# MATRIZ_8x8.net
KiCad netlist of a schematic drawn in EAGLE
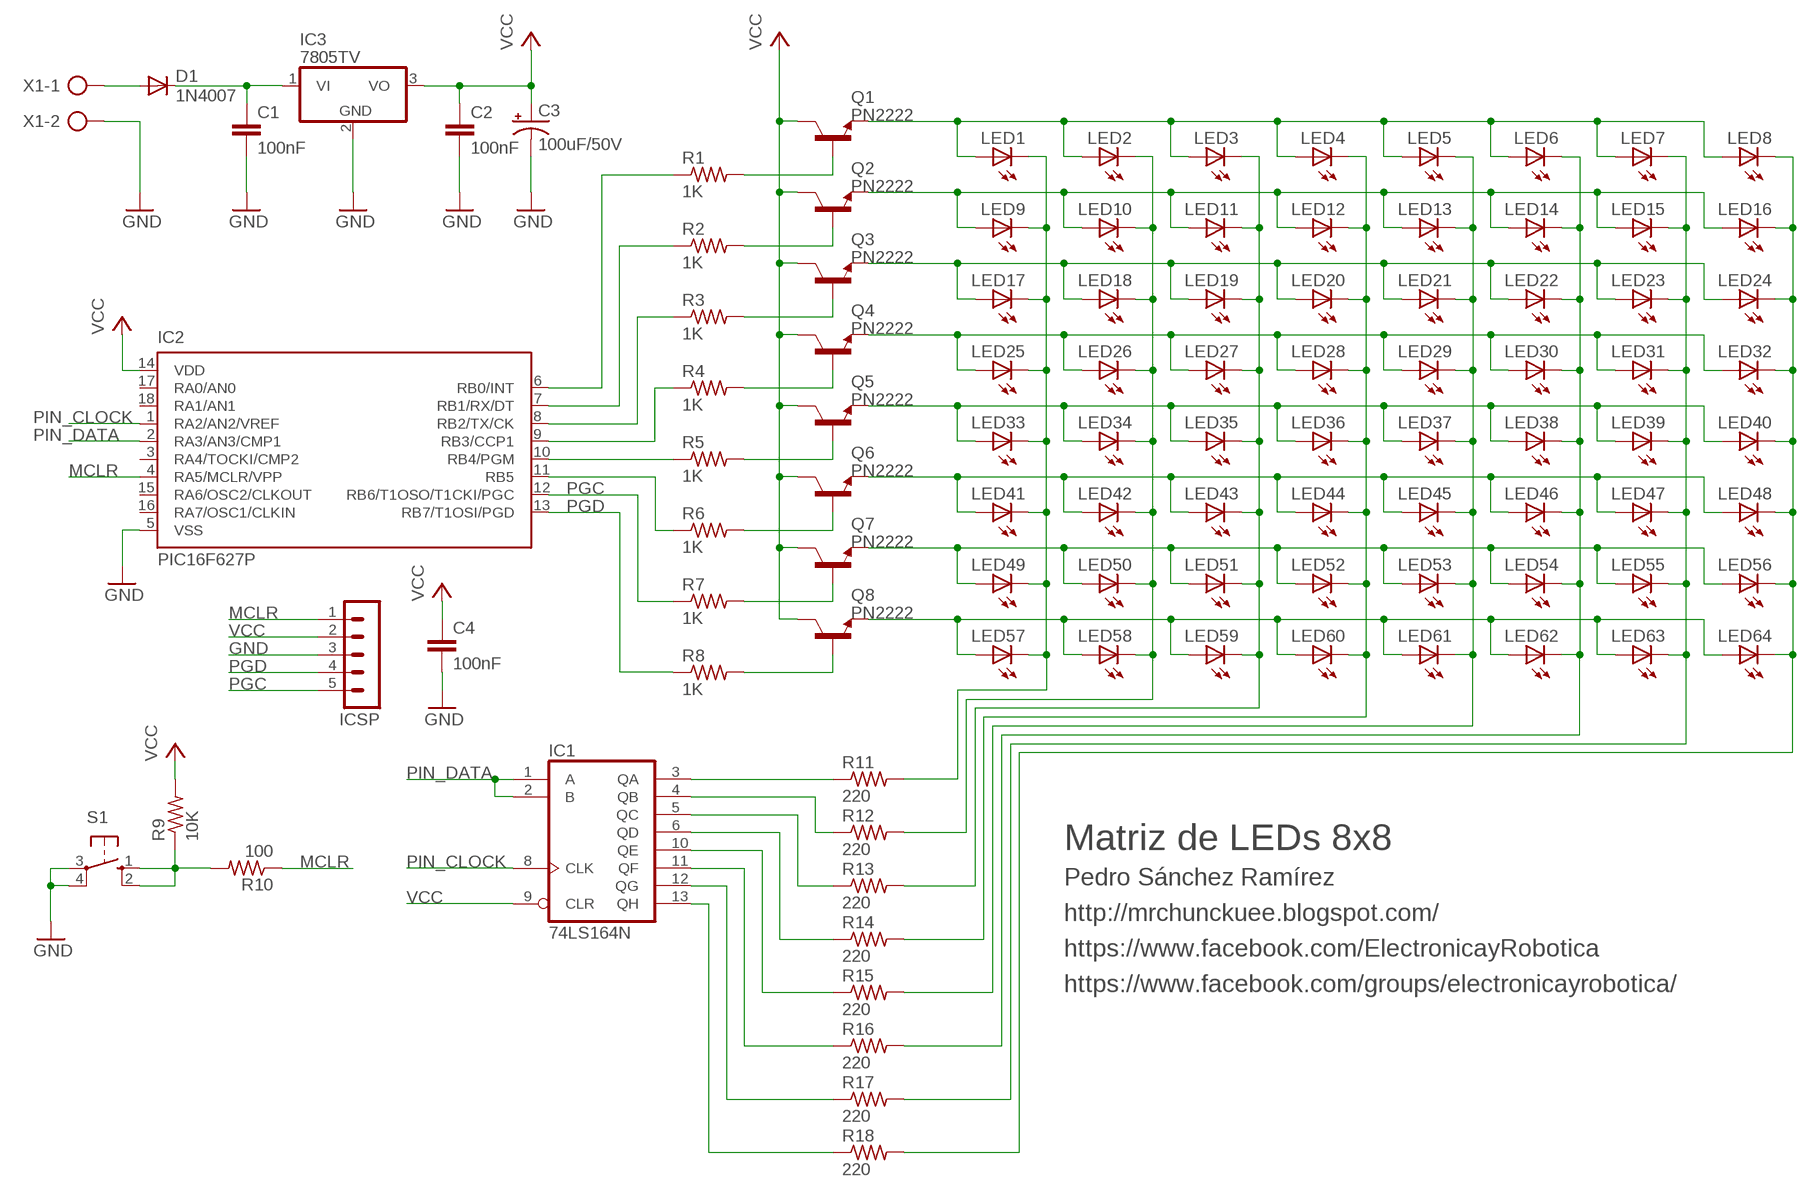
[diagram p0: schematic, sheet 1]

(export (version "E")
  (design (tool "Eeschema 10.0.6"))
  (components
    (comp (ref "C1")
      (value "100nF")
      (footprint "eagle-import:C050-024X044")
      (libsource (lib "eagle-import") (part "C-EU050-024X044"))
    )
    (comp (ref "C2")
      (value "100nF")
      (footprint "eagle-import:C050-024X044")
      (libsource (lib "eagle-import") (part "C-EU050-024X044"))
    )
    (comp (ref "C3")
      (value "100uF/50V")
      (footprint "eagle-import:E5-10,5")
      (libsource (lib "eagle-import") (part "CPOL-USE5-10.5"))
    )
    (comp (ref "C4")
      (value "100nF")
      (footprint "eagle-import:C050-024X044")
      (libsource (lib "eagle-import") (part "C-EU050-024X044"))
    )
    (comp (ref "D1")
      (value "1N4007")
      (footprint "eagle-import:DO41-10")
      (libsource (lib "eagle-import") (part "1N4004"))
    )
    (comp (ref "IC1")
      (value "74LS164N")
      (footprint "eagle-import:DIL14")
      (libsource (lib "eagle-import") (part "74164NLS"))
    )
    (comp (ref "IC2")
      (value "PIC16F627P")
      (footprint "eagle-import:DIL18")
      (fields (field (name "MF") "MICROCHIP") (field (name "MPN") "PIC16F627-04/P"))
      (libsource (lib "eagle-import") (part "PIC16F62P7"))
    )
    (comp (ref "IC3")
      (value "7805TV")
      (footprint "eagle-import:TO220V")
      (libsource (lib "eagle-import") (part "78TV05"))
    )
    (comp (ref "ICSP")
      (value "MA05-1")
      (footprint "eagle-import:MA05-1")
      (libsource (lib "eagle-import") (part "MA05-1"))
    )
    (comp (ref "LED1")
      (value "LED5MM")
      (footprint "eagle-import:LED5MM")
      (libsource (lib "eagle-import") (part "LED5MM"))
    )
    (comp (ref "LED2")
      (value "LED5MM")
      (footprint "eagle-import:LED5MM")
      (libsource (lib "eagle-import") (part "LED5MM"))
    )
    (comp (ref "LED3")
      (value "LED5MM")
      (footprint "eagle-import:LED5MM")
      (libsource (lib "eagle-import") (part "LED5MM"))
    )
    (comp (ref "LED4")
      (value "LED5MM")
      (footprint "eagle-import:LED5MM")
      (libsource (lib "eagle-import") (part "LED5MM"))
    )
    (comp (ref "LED5")
      (value "LED5MM")
      (footprint "eagle-import:LED5MM")
      (libsource (lib "eagle-import") (part "LED5MM"))
    )
    (comp (ref "LED6")
      (value "LED5MM")
      (footprint "eagle-import:LED5MM")
      (libsource (lib "eagle-import") (part "LED5MM"))
    )
    (comp (ref "LED7")
      (value "LED5MM")
      (footprint "eagle-import:LED5MM")
      (libsource (lib "eagle-import") (part "LED5MM"))
    )
    (comp (ref "LED8")
      (value "LED5MM")
      (footprint "eagle-import:LED5MM")
      (libsource (lib "eagle-import") (part "LED5MM"))
    )
    (comp (ref "LED9")
      (value "LED5MM")
      (footprint "eagle-import:LED5MM")
      (libsource (lib "eagle-import") (part "LED5MM"))
    )
    (comp (ref "LED10")
      (value "LED5MM")
      (footprint "eagle-import:LED5MM")
      (libsource (lib "eagle-import") (part "LED5MM"))
    )
    (comp (ref "LED11")
      (value "LED5MM")
      (footprint "eagle-import:LED5MM")
      (libsource (lib "eagle-import") (part "LED5MM"))
    )
    (comp (ref "LED12")
      (value "LED5MM")
      (footprint "eagle-import:LED5MM")
      (libsource (lib "eagle-import") (part "LED5MM"))
    )
    (comp (ref "LED13")
      (value "LED5MM")
      (footprint "eagle-import:LED5MM")
      (libsource (lib "eagle-import") (part "LED5MM"))
    )
    (comp (ref "LED14")
      (value "LED5MM")
      (footprint "eagle-import:LED5MM")
      (libsource (lib "eagle-import") (part "LED5MM"))
    )
    (comp (ref "LED15")
      (value "LED5MM")
      (footprint "eagle-import:LED5MM")
      (libsource (lib "eagle-import") (part "LED5MM"))
    )
    (comp (ref "LED16")
      (value "LED5MM")
      (footprint "eagle-import:LED5MM")
      (libsource (lib "eagle-import") (part "LED5MM"))
    )
    (comp (ref "LED17")
      (value "LED5MM")
      (footprint "eagle-import:LED5MM")
      (libsource (lib "eagle-import") (part "LED5MM"))
    )
    (comp (ref "LED18")
      (value "LED5MM")
      (footprint "eagle-import:LED5MM")
      (libsource (lib "eagle-import") (part "LED5MM"))
    )
    (comp (ref "LED19")
      (value "LED5MM")
      (footprint "eagle-import:LED5MM")
      (libsource (lib "eagle-import") (part "LED5MM"))
    )
    (comp (ref "LED20")
      (value "LED5MM")
      (footprint "eagle-import:LED5MM")
      (libsource (lib "eagle-import") (part "LED5MM"))
    )
    (comp (ref "LED21")
      (value "LED5MM")
      (footprint "eagle-import:LED5MM")
      (libsource (lib "eagle-import") (part "LED5MM"))
    )
    (comp (ref "LED22")
      (value "LED5MM")
      (footprint "eagle-import:LED5MM")
      (libsource (lib "eagle-import") (part "LED5MM"))
    )
    (comp (ref "LED23")
      (value "LED5MM")
      (footprint "eagle-import:LED5MM")
      (libsource (lib "eagle-import") (part "LED5MM"))
    )
    (comp (ref "LED24")
      (value "LED5MM")
      (footprint "eagle-import:LED5MM")
      (libsource (lib "eagle-import") (part "LED5MM"))
    )
    (comp (ref "LED25")
      (value "LED5MM")
      (footprint "eagle-import:LED5MM")
      (libsource (lib "eagle-import") (part "LED5MM"))
    )
    (comp (ref "LED26")
      (value "LED5MM")
      (footprint "eagle-import:LED5MM")
      (libsource (lib "eagle-import") (part "LED5MM"))
    )
    (comp (ref "LED27")
      (value "LED5MM")
      (footprint "eagle-import:LED5MM")
      (libsource (lib "eagle-import") (part "LED5MM"))
    )
    (comp (ref "LED28")
      (value "LED5MM")
      (footprint "eagle-import:LED5MM")
      (libsource (lib "eagle-import") (part "LED5MM"))
    )
    (comp (ref "LED29")
      (value "LED5MM")
      (footprint "eagle-import:LED5MM")
      (libsource (lib "eagle-import") (part "LED5MM"))
    )
    (comp (ref "LED30")
      (value "LED5MM")
      (footprint "eagle-import:LED5MM")
      (libsource (lib "eagle-import") (part "LED5MM"))
    )
    (comp (ref "LED31")
      (value "LED5MM")
      (footprint "eagle-import:LED5MM")
      (libsource (lib "eagle-import") (part "LED5MM"))
    )
    (comp (ref "LED32")
      (value "LED5MM")
      (footprint "eagle-import:LED5MM")
      (libsource (lib "eagle-import") (part "LED5MM"))
    )
    (comp (ref "LED33")
      (value "LED5MM")
      (footprint "eagle-import:LED5MM")
      (libsource (lib "eagle-import") (part "LED5MM"))
    )
    (comp (ref "LED34")
      (value "LED5MM")
      (footprint "eagle-import:LED5MM")
      (libsource (lib "eagle-import") (part "LED5MM"))
    )
    (comp (ref "LED35")
      (value "LED5MM")
      (footprint "eagle-import:LED5MM")
      (libsource (lib "eagle-import") (part "LED5MM"))
    )
    (comp (ref "LED36")
      (value "LED5MM")
      (footprint "eagle-import:LED5MM")
      (libsource (lib "eagle-import") (part "LED5MM"))
    )
    (comp (ref "LED37")
      (value "LED5MM")
      (footprint "eagle-import:LED5MM")
      (libsource (lib "eagle-import") (part "LED5MM"))
    )
    (comp (ref "LED38")
      (value "LED5MM")
      (footprint "eagle-import:LED5MM")
      (libsource (lib "eagle-import") (part "LED5MM"))
    )
    (comp (ref "LED39")
      (value "LED5MM")
      (footprint "eagle-import:LED5MM")
      (libsource (lib "eagle-import") (part "LED5MM"))
    )
    (comp (ref "LED40")
      (value "LED5MM")
      (footprint "eagle-import:LED5MM")
      (libsource (lib "eagle-import") (part "LED5MM"))
    )
    (comp (ref "LED41")
      (value "LED5MM")
      (footprint "eagle-import:LED5MM")
      (libsource (lib "eagle-import") (part "LED5MM"))
    )
    (comp (ref "LED42")
      (value "LED5MM")
      (footprint "eagle-import:LED5MM")
      (libsource (lib "eagle-import") (part "LED5MM"))
    )
    (comp (ref "LED43")
      (value "LED5MM")
      (footprint "eagle-import:LED5MM")
      (libsource (lib "eagle-import") (part "LED5MM"))
    )
    (comp (ref "LED44")
      (value "LED5MM")
      (footprint "eagle-import:LED5MM")
      (libsource (lib "eagle-import") (part "LED5MM"))
    )
    (comp (ref "LED45")
      (value "LED5MM")
      (footprint "eagle-import:LED5MM")
      (libsource (lib "eagle-import") (part "LED5MM"))
    )
    (comp (ref "LED46")
      (value "LED5MM")
      (footprint "eagle-import:LED5MM")
      (libsource (lib "eagle-import") (part "LED5MM"))
    )
    (comp (ref "LED47")
      (value "LED5MM")
      (footprint "eagle-import:LED5MM")
      (libsource (lib "eagle-import") (part "LED5MM"))
    )
    (comp (ref "LED48")
      (value "LED5MM")
      (footprint "eagle-import:LED5MM")
      (libsource (lib "eagle-import") (part "LED5MM"))
    )
    (comp (ref "LED49")
      (value "LED5MM")
      (footprint "eagle-import:LED5MM")
      (libsource (lib "eagle-import") (part "LED5MM"))
    )
    (comp (ref "LED50")
      (value "LED5MM")
      (footprint "eagle-import:LED5MM")
      (libsource (lib "eagle-import") (part "LED5MM"))
    )
    (comp (ref "LED51")
      (value "LED5MM")
      (footprint "eagle-import:LED5MM")
      (libsource (lib "eagle-import") (part "LED5MM"))
    )
    (comp (ref "LED52")
      (value "LED5MM")
      (footprint "eagle-import:LED5MM")
      (libsource (lib "eagle-import") (part "LED5MM"))
    )
    (comp (ref "LED53")
      (value "LED5MM")
      (footprint "eagle-import:LED5MM")
      (libsource (lib "eagle-import") (part "LED5MM"))
    )
    (comp (ref "LED54")
      (value "LED5MM")
      (footprint "eagle-import:LED5MM")
      (libsource (lib "eagle-import") (part "LED5MM"))
    )
    (comp (ref "LED55")
      (value "LED5MM")
      (footprint "eagle-import:LED5MM")
      (libsource (lib "eagle-import") (part "LED5MM"))
    )
    (comp (ref "LED56")
      (value "LED5MM")
      (footprint "eagle-import:LED5MM")
      (libsource (lib "eagle-import") (part "LED5MM"))
    )
    (comp (ref "LED57")
      (value "LED5MM")
      (footprint "eagle-import:LED5MM")
      (libsource (lib "eagle-import") (part "LED5MM"))
    )
    (comp (ref "LED58")
      (value "LED5MM")
      (footprint "eagle-import:LED5MM")
      (libsource (lib "eagle-import") (part "LED5MM"))
    )
    (comp (ref "LED59")
      (value "LED5MM")
      (footprint "eagle-import:LED5MM")
      (libsource (lib "eagle-import") (part "LED5MM"))
    )
    (comp (ref "LED60")
      (value "LED5MM")
      (footprint "eagle-import:LED5MM")
      (libsource (lib "eagle-import") (part "LED5MM"))
    )
    (comp (ref "LED61")
      (value "LED5MM")
      (footprint "eagle-import:LED5MM")
      (libsource (lib "eagle-import") (part "LED5MM"))
    )
    (comp (ref "LED62")
      (value "LED5MM")
      (footprint "eagle-import:LED5MM")
      (libsource (lib "eagle-import") (part "LED5MM"))
    )
    (comp (ref "LED63")
      (value "LED5MM")
      (footprint "eagle-import:LED5MM")
      (libsource (lib "eagle-import") (part "LED5MM"))
    )
    (comp (ref "LED64")
      (value "LED5MM")
      (footprint "eagle-import:LED5MM")
      (libsource (lib "eagle-import") (part "LED5MM"))
    )
    (comp (ref "Q1")
      (value "PN2222")
      (footprint "eagle-import:TO92-EBC")
      (libsource (lib "eagle-import") (part "-NPN-TO92-EBC2N4124"))
    )
    (comp (ref "Q2")
      (value "PN2222")
      (footprint "eagle-import:TO92-EBC")
      (libsource (lib "eagle-import") (part "-NPN-TO92-EBC2N4124"))
    )
    (comp (ref "Q3")
      (value "PN2222")
      (footprint "eagle-import:TO92-EBC")
      (libsource (lib "eagle-import") (part "-NPN-TO92-EBC2N4124"))
    )
    (comp (ref "Q4")
      (value "PN2222")
      (footprint "eagle-import:TO92-EBC")
      (libsource (lib "eagle-import") (part "-NPN-TO92-EBC2N4124"))
    )
    (comp (ref "Q5")
      (value "PN2222")
      (footprint "eagle-import:TO92-EBC")
      (libsource (lib "eagle-import") (part "-NPN-TO92-EBC2N4124"))
    )
    (comp (ref "Q6")
      (value "PN2222")
      (footprint "eagle-import:TO92-EBC")
      (libsource (lib "eagle-import") (part "-NPN-TO92-EBC2N4124"))
    )
    (comp (ref "Q7")
      (value "PN2222")
      (footprint "eagle-import:TO92-EBC")
      (libsource (lib "eagle-import") (part "-NPN-TO92-EBC2N4124"))
    )
    (comp (ref "Q8")
      (value "PN2222")
      (footprint "eagle-import:TO92-EBC")
      (libsource (lib "eagle-import") (part "-NPN-TO92-EBC2N4124"))
    )
    (comp (ref "R1")
      (value "1K")
      (footprint "eagle-import:0204_7")
      (libsource (lib "eagle-import") (part "R-US_0204/7"))
    )
    (comp (ref "R2")
      (value "1K")
      (footprint "eagle-import:0204_7")
      (libsource (lib "eagle-import") (part "R-US_0204/7"))
    )
    (comp (ref "R3")
      (value "1K")
      (footprint "eagle-import:0204_7")
      (libsource (lib "eagle-import") (part "R-US_0204/7"))
    )
    (comp (ref "R4")
      (value "1K")
      (footprint "eagle-import:0204_7")
      (libsource (lib "eagle-import") (part "R-US_0204/7"))
    )
    (comp (ref "R5")
      (value "1K")
      (footprint "eagle-import:0204_7")
      (libsource (lib "eagle-import") (part "R-US_0204/7"))
    )
    (comp (ref "R6")
      (value "1K")
      (footprint "eagle-import:0204_7")
      (libsource (lib "eagle-import") (part "R-US_0204/7"))
    )
    (comp (ref "R7")
      (value "1K")
      (footprint "eagle-import:0204_7")
      (libsource (lib "eagle-import") (part "R-US_0204/7"))
    )
    (comp (ref "R8")
      (value "1K")
      (footprint "eagle-import:0204_7")
      (libsource (lib "eagle-import") (part "R-US_0204/7"))
    )
    (comp (ref "R9")
      (value "10K")
      (footprint "eagle-import:0204_7")
      (libsource (lib "eagle-import") (part "R-US_0204/7"))
    )
    (comp (ref "R10")
      (value "100")
      (footprint "eagle-import:0204_7")
      (libsource (lib "eagle-import") (part "R-US_0204/7"))
    )
    (comp (ref "R11")
      (value "220")
      (footprint "eagle-import:0204_7")
      (libsource (lib "eagle-import") (part "R-US_0204/7"))
    )
    (comp (ref "R12")
      (value "220")
      (footprint "eagle-import:0204_7")
      (libsource (lib "eagle-import") (part "R-US_0204/7"))
    )
    (comp (ref "R13")
      (value "220")
      (footprint "eagle-import:0204_7")
      (libsource (lib "eagle-import") (part "R-US_0204/7"))
    )
    (comp (ref "R14")
      (value "220")
      (footprint "eagle-import:0204_7")
      (libsource (lib "eagle-import") (part "R-US_0204/7"))
    )
    (comp (ref "R15")
      (value "220")
      (footprint "eagle-import:0204_7")
      (libsource (lib "eagle-import") (part "R-US_0204/7"))
    )
    (comp (ref "R16")
      (value "220")
      (footprint "eagle-import:0204_7")
      (libsource (lib "eagle-import") (part "R-US_0204/7"))
    )
    (comp (ref "R17")
      (value "220")
      (footprint "eagle-import:0204_7")
      (libsource (lib "eagle-import") (part "R-US_0204/7"))
    )
    (comp (ref "R18")
      (value "220")
      (footprint "eagle-import:0204_7")
      (libsource (lib "eagle-import") (part "R-US_0204/7"))
    )
    (comp (ref "S1")
      (value "10-XX")
      (footprint "eagle-import:B3F-10XX")
      (fields (field (name "MPN") "B3F-1000"))
      (libsource (lib "eagle-import") (part "10-XX"))
    )
    (comp (ref "X1")
      (value "AK500/2-H")
      (footprint "eagle-import:AK500_2-H")
      (libsource (lib "eagle-import") (part "AK500/2-H"))
    )
  )
  (nets
    (net (code "1") (name "/MCLR") (class "Default")
      (node (ref "IC2") (pin "4") (pinfunction "RA5/MCLR/VPP_4") (pintype "bidirectional"))
      (node (ref "ICSP") (pin "1") (pinfunction "1_1") (pintype "passive"))
      (node (ref "R10") (pin "1") (pinfunction "1_1") (pintype "passive"))
    )
    (net (code "2") (name "/PGC") (class "Default")
      (node (ref "IC2") (pin "12") (pinfunction "RB6/T1OSO/T1CKI/PGC_12") (pintype "bidirectional"))
      (node (ref "ICSP") (pin "5") (pinfunction "5_5") (pintype "passive"))
      (node (ref "R7") (pin "1") (pinfunction "1_1") (pintype "passive"))
    )
    (net (code "3") (name "/PGD") (class "Default")
      (node (ref "IC2") (pin "13") (pinfunction "RB7/T1OSI/PGD_13") (pintype "bidirectional"))
      (node (ref "ICSP") (pin "4") (pinfunction "4_4") (pintype "passive"))
      (node (ref "R8") (pin "1") (pinfunction "1_1") (pintype "passive"))
    )
    (net (code "4") (name "/PIN_CLOCK") (class "Default")
      (node (ref "IC1") (pin "8") (pinfunction "CLK_8") (pintype "input"))
      (node (ref "IC2") (pin "1") (pinfunction "RA2/AN2/VREF_1") (pintype "bidirectional"))
    )
    (net (code "5") (name "/PIN_DATA") (class "Default")
      (node (ref "IC1") (pin "1") (pinfunction "A_1") (pintype "input"))
      (node (ref "IC1") (pin "2") (pinfunction "B_2") (pintype "input"))
      (node (ref "IC2") (pin "2") (pinfunction "RA3/AN3/CMP1_2") (pintype "bidirectional"))
    )
    (net (code "6") (name "GND") (class "Default")
      (node (ref "C1") (pin "2") (pinfunction "2_2") (pintype "passive"))
      (node (ref "C2") (pin "2") (pinfunction "2_2") (pintype "passive"))
      (node (ref "C3") (pin "-") (pinfunction "-_-") (pintype "passive"))
      (node (ref "C4") (pin "2") (pinfunction "2_2") (pintype "passive"))
      (node (ref "IC2") (pin "5") (pinfunction "VSS_5") (pintype "power_in"))
      (node (ref "IC3") (pin "2") (pinfunction "GND_2") (pintype "passive"))
      (node (ref "ICSP") (pin "3") (pinfunction "3_3") (pintype "passive"))
      (node (ref "S1") (pin "3") (pinfunction "P_3") (pintype "passive"))
      (node (ref "S1") (pin "4") (pinfunction "P1_4") (pintype "passive"))
      (node (ref "X1") (pin "2") (pinfunction "KL_2") (pintype "passive"))
    )
    (net (code "7") (name "Net-(IC1A-QA)") (class "Default")
      (node (ref "IC1") (pin "3") (pinfunction "QA_3") (pintype "output"))
      (node (ref "R11") (pin "1") (pinfunction "1_1") (pintype "passive"))
    )
    (net (code "8") (name "Net-(IC1A-QB)") (class "Default")
      (node (ref "IC1") (pin "4") (pinfunction "QB_4") (pintype "output"))
      (node (ref "R12") (pin "1") (pinfunction "1_1") (pintype "passive"))
    )
    (net (code "9") (name "Net-(IC1A-QC)") (class "Default")
      (node (ref "IC1") (pin "5") (pinfunction "QC_5") (pintype "output"))
      (node (ref "R13") (pin "1") (pinfunction "1_1") (pintype "passive"))
    )
    (net (code "10") (name "Net-(IC1A-QD)") (class "Default")
      (node (ref "IC1") (pin "6") (pinfunction "QD_6") (pintype "output"))
      (node (ref "R14") (pin "1") (pinfunction "1_1") (pintype "passive"))
    )
    (net (code "11") (name "Net-(IC1A-QE)") (class "Default")
      (node (ref "IC1") (pin "10") (pinfunction "QE_10") (pintype "output"))
      (node (ref "R15") (pin "1") (pinfunction "1_1") (pintype "passive"))
    )
    (net (code "12") (name "Net-(IC1A-QF)") (class "Default")
      (node (ref "IC1") (pin "11") (pinfunction "QF_11") (pintype "output"))
      (node (ref "R16") (pin "1") (pinfunction "1_1") (pintype "passive"))
    )
    (net (code "13") (name "Net-(IC1A-QG)") (class "Default")
      (node (ref "IC1") (pin "12") (pinfunction "QG_12") (pintype "output"))
      (node (ref "R17") (pin "1") (pinfunction "1_1") (pintype "passive"))
    )
    (net (code "14") (name "Net-(IC1A-QH)") (class "Default")
      (node (ref "IC1") (pin "13") (pinfunction "QH_13") (pintype "output"))
      (node (ref "R18") (pin "1") (pinfunction "1_1") (pintype "passive"))
    )
    (net (code "15") (name "Net-(IC2-RB0{slash}INT)") (class "Default")
      (node (ref "IC2") (pin "6") (pinfunction "RB0/INT_6") (pintype "bidirectional"))
      (node (ref "R1") (pin "1") (pinfunction "1_1") (pintype "passive"))
    )
    (net (code "16") (name "Net-(IC2-RB1{slash}RX{slash}DT)") (class "Default")
      (node (ref "IC2") (pin "7") (pinfunction "RB1/RX/DT_7") (pintype "bidirectional"))
      (node (ref "R2") (pin "1") (pinfunction "1_1") (pintype "passive"))
    )
    (net (code "17") (name "Net-(IC2-RB2{slash}TX{slash}CK)") (class "Default")
      (node (ref "IC2") (pin "8") (pinfunction "RB2/TX/CK_8") (pintype "bidirectional"))
      (node (ref "R3") (pin "1") (pinfunction "1_1") (pintype "passive"))
    )
    (net (code "18") (name "Net-(IC2-RB3{slash}CCP1)") (class "Default")
      (node (ref "IC2") (pin "9") (pinfunction "RB3/CCP1_9") (pintype "bidirectional"))
      (node (ref "R4") (pin "1") (pinfunction "1_1") (pintype "passive"))
    )
    (net (code "19") (name "Net-(IC2-RB4{slash}PGM)") (class "Default")
      (node (ref "IC2") (pin "10") (pinfunction "RB4/PGM_10") (pintype "bidirectional"))
      (node (ref "R5") (pin "1") (pinfunction "1_1") (pintype "passive"))
    )
    (net (code "20") (name "Net-(IC2-RB5)") (class "Default")
      (node (ref "IC2") (pin "11") (pinfunction "RB5_11") (pintype "bidirectional"))
      (node (ref "R6") (pin "1") (pinfunction "1_1") (pintype "passive"))
    )
    (net (code "21") (name "Net-(IC3-VI)") (class "Default")
      (node (ref "C1") (pin "1") (pinfunction "1_1") (pintype "passive"))
      (node (ref "D1") (pin "C") (pinfunction "C_C") (pintype "passive"))
      (node (ref "IC3") (pin "1") (pinfunction "VI_1") (pintype "input"))
    )
    (net (code "22") (name "Net-(LED1-C)") (class "Default")
      (node (ref "LED1") (pin "K") (pinfunction "C_K") (pintype "passive"))
      (node (ref "LED17") (pin "K") (pinfunction "C_K") (pintype "passive"))
      (node (ref "LED25") (pin "K") (pinfunction "C_K") (pintype "passive"))
      (node (ref "LED33") (pin "K") (pinfunction "C_K") (pintype "passive"))
      (node (ref "LED41") (pin "K") (pinfunction "C_K") (pintype "passive"))
      (node (ref "LED49") (pin "K") (pinfunction "C_K") (pintype "passive"))
      (node (ref "LED57") (pin "K") (pinfunction "C_K") (pintype "passive"))
      (node (ref "LED9") (pin "K") (pinfunction "C_K") (pintype "passive"))
      (node (ref "R11") (pin "2") (pinfunction "2_2") (pintype "passive"))
    )
    (net (code "23") (name "Net-(LED1-PadA)") (class "Default")
      (node (ref "LED1") (pin "A") (pinfunction "A_A") (pintype "passive"))
      (node (ref "LED2") (pin "A") (pinfunction "A_A") (pintype "passive"))
      (node (ref "LED3") (pin "A") (pinfunction "A_A") (pintype "passive"))
      (node (ref "LED4") (pin "A") (pinfunction "A_A") (pintype "passive"))
      (node (ref "LED5") (pin "A") (pinfunction "A_A") (pintype "passive"))
      (node (ref "LED6") (pin "A") (pinfunction "A_A") (pintype "passive"))
      (node (ref "LED7") (pin "A") (pinfunction "A_A") (pintype "passive"))
      (node (ref "LED8") (pin "A") (pinfunction "A_A") (pintype "passive"))
      (node (ref "Q1") (pin "E") (pinfunction "E_E") (pintype "passive"))
    )
    (net (code "24") (name "Net-(LED10-C)") (class "Default")
      (node (ref "LED10") (pin "K") (pinfunction "C_K") (pintype "passive"))
      (node (ref "LED18") (pin "K") (pinfunction "C_K") (pintype "passive"))
      (node (ref "LED2") (pin "K") (pinfunction "C_K") (pintype "passive"))
      (node (ref "LED26") (pin "K") (pinfunction "C_K") (pintype "passive"))
      (node (ref "LED34") (pin "K") (pinfunction "C_K") (pintype "passive"))
      (node (ref "LED42") (pin "K") (pinfunction "C_K") (pintype "passive"))
      (node (ref "LED50") (pin "K") (pinfunction "C_K") (pintype "passive"))
      (node (ref "LED58") (pin "K") (pinfunction "C_K") (pintype "passive"))
      (node (ref "R12") (pin "2") (pinfunction "2_2") (pintype "passive"))
    )
    (net (code "25") (name "Net-(LED10-PadA)") (class "Default")
      (node (ref "LED10") (pin "A") (pinfunction "A_A") (pintype "passive"))
      (node (ref "LED11") (pin "A") (pinfunction "A_A") (pintype "passive"))
      (node (ref "LED12") (pin "A") (pinfunction "A_A") (pintype "passive"))
      (node (ref "LED13") (pin "A") (pinfunction "A_A") (pintype "passive"))
      (node (ref "LED14") (pin "A") (pinfunction "A_A") (pintype "passive"))
      (node (ref "LED15") (pin "A") (pinfunction "A_A") (pintype "passive"))
      (node (ref "LED16") (pin "A") (pinfunction "A_A") (pintype "passive"))
      (node (ref "LED9") (pin "A") (pinfunction "A_A") (pintype "passive"))
      (node (ref "Q2") (pin "E") (pinfunction "E_E") (pintype "passive"))
    )
    (net (code "26") (name "Net-(LED11-C)") (class "Default")
      (node (ref "LED11") (pin "K") (pinfunction "C_K") (pintype "passive"))
      (node (ref "LED19") (pin "K") (pinfunction "C_K") (pintype "passive"))
      (node (ref "LED27") (pin "K") (pinfunction "C_K") (pintype "passive"))
      (node (ref "LED3") (pin "K") (pinfunction "C_K") (pintype "passive"))
      (node (ref "LED35") (pin "K") (pinfunction "C_K") (pintype "passive"))
      (node (ref "LED43") (pin "K") (pinfunction "C_K") (pintype "passive"))
      (node (ref "LED51") (pin "K") (pinfunction "C_K") (pintype "passive"))
      (node (ref "LED59") (pin "K") (pinfunction "C_K") (pintype "passive"))
      (node (ref "R13") (pin "2") (pinfunction "2_2") (pintype "passive"))
    )
    (net (code "27") (name "Net-(LED12-C)") (class "Default")
      (node (ref "LED12") (pin "K") (pinfunction "C_K") (pintype "passive"))
      (node (ref "LED20") (pin "K") (pinfunction "C_K") (pintype "passive"))
      (node (ref "LED28") (pin "K") (pinfunction "C_K") (pintype "passive"))
      (node (ref "LED36") (pin "K") (pinfunction "C_K") (pintype "passive"))
      (node (ref "LED4") (pin "K") (pinfunction "C_K") (pintype "passive"))
      (node (ref "LED44") (pin "K") (pinfunction "C_K") (pintype "passive"))
      (node (ref "LED52") (pin "K") (pinfunction "C_K") (pintype "passive"))
      (node (ref "LED60") (pin "K") (pinfunction "C_K") (pintype "passive"))
      (node (ref "R14") (pin "2") (pinfunction "2_2") (pintype "passive"))
    )
    (net (code "28") (name "Net-(LED13-C)") (class "Default")
      (node (ref "LED13") (pin "K") (pinfunction "C_K") (pintype "passive"))
      (node (ref "LED21") (pin "K") (pinfunction "C_K") (pintype "passive"))
      (node (ref "LED29") (pin "K") (pinfunction "C_K") (pintype "passive"))
      (node (ref "LED37") (pin "K") (pinfunction "C_K") (pintype "passive"))
      (node (ref "LED45") (pin "K") (pinfunction "C_K") (pintype "passive"))
      (node (ref "LED5") (pin "K") (pinfunction "C_K") (pintype "passive"))
      (node (ref "LED53") (pin "K") (pinfunction "C_K") (pintype "passive"))
      (node (ref "LED61") (pin "K") (pinfunction "C_K") (pintype "passive"))
      (node (ref "R15") (pin "2") (pinfunction "2_2") (pintype "passive"))
    )
    (net (code "29") (name "Net-(LED14-C)") (class "Default")
      (node (ref "LED14") (pin "K") (pinfunction "C_K") (pintype "passive"))
      (node (ref "LED22") (pin "K") (pinfunction "C_K") (pintype "passive"))
      (node (ref "LED30") (pin "K") (pinfunction "C_K") (pintype "passive"))
      (node (ref "LED38") (pin "K") (pinfunction "C_K") (pintype "passive"))
      (node (ref "LED46") (pin "K") (pinfunction "C_K") (pintype "passive"))
      (node (ref "LED54") (pin "K") (pinfunction "C_K") (pintype "passive"))
      (node (ref "LED6") (pin "K") (pinfunction "C_K") (pintype "passive"))
      (node (ref "LED62") (pin "K") (pinfunction "C_K") (pintype "passive"))
      (node (ref "R16") (pin "2") (pinfunction "2_2") (pintype "passive"))
    )
    (net (code "30") (name "Net-(LED15-C)") (class "Default")
      (node (ref "LED15") (pin "K") (pinfunction "C_K") (pintype "passive"))
      (node (ref "LED23") (pin "K") (pinfunction "C_K") (pintype "passive"))
      (node (ref "LED31") (pin "K") (pinfunction "C_K") (pintype "passive"))
      (node (ref "LED39") (pin "K") (pinfunction "C_K") (pintype "passive"))
      (node (ref "LED47") (pin "K") (pinfunction "C_K") (pintype "passive"))
      (node (ref "LED55") (pin "K") (pinfunction "C_K") (pintype "passive"))
      (node (ref "LED63") (pin "K") (pinfunction "C_K") (pintype "passive"))
      (node (ref "LED7") (pin "K") (pinfunction "C_K") (pintype "passive"))
      (node (ref "R17") (pin "2") (pinfunction "2_2") (pintype "passive"))
    )
    (net (code "31") (name "Net-(LED16-C)") (class "Default")
      (node (ref "LED16") (pin "K") (pinfunction "C_K") (pintype "passive"))
      (node (ref "LED24") (pin "K") (pinfunction "C_K") (pintype "passive"))
      (node (ref "LED32") (pin "K") (pinfunction "C_K") (pintype "passive"))
      (node (ref "LED40") (pin "K") (pinfunction "C_K") (pintype "passive"))
      (node (ref "LED48") (pin "K") (pinfunction "C_K") (pintype "passive"))
      (node (ref "LED56") (pin "K") (pinfunction "C_K") (pintype "passive"))
      (node (ref "LED64") (pin "K") (pinfunction "C_K") (pintype "passive"))
      (node (ref "LED8") (pin "K") (pinfunction "C_K") (pintype "passive"))
      (node (ref "R18") (pin "2") (pinfunction "2_2") (pintype "passive"))
    )
    (net (code "32") (name "Net-(LED17-PadA)") (class "Default")
      (node (ref "LED17") (pin "A") (pinfunction "A_A") (pintype "passive"))
      (node (ref "LED18") (pin "A") (pinfunction "A_A") (pintype "passive"))
      (node (ref "LED19") (pin "A") (pinfunction "A_A") (pintype "passive"))
      (node (ref "LED20") (pin "A") (pinfunction "A_A") (pintype "passive"))
      (node (ref "LED21") (pin "A") (pinfunction "A_A") (pintype "passive"))
      (node (ref "LED22") (pin "A") (pinfunction "A_A") (pintype "passive"))
      (node (ref "LED23") (pin "A") (pinfunction "A_A") (pintype "passive"))
      (node (ref "LED24") (pin "A") (pinfunction "A_A") (pintype "passive"))
      (node (ref "Q3") (pin "E") (pinfunction "E_E") (pintype "passive"))
    )
    (net (code "33") (name "Net-(LED25-PadA)") (class "Default")
      (node (ref "LED25") (pin "A") (pinfunction "A_A") (pintype "passive"))
      (node (ref "LED26") (pin "A") (pinfunction "A_A") (pintype "passive"))
      (node (ref "LED27") (pin "A") (pinfunction "A_A") (pintype "passive"))
      (node (ref "LED28") (pin "A") (pinfunction "A_A") (pintype "passive"))
      (node (ref "LED29") (pin "A") (pinfunction "A_A") (pintype "passive"))
      (node (ref "LED30") (pin "A") (pinfunction "A_A") (pintype "passive"))
      (node (ref "LED31") (pin "A") (pinfunction "A_A") (pintype "passive"))
      (node (ref "LED32") (pin "A") (pinfunction "A_A") (pintype "passive"))
      (node (ref "Q4") (pin "E") (pinfunction "E_E") (pintype "passive"))
    )
    (net (code "34") (name "Net-(LED33-PadA)") (class "Default")
      (node (ref "LED33") (pin "A") (pinfunction "A_A") (pintype "passive"))
      (node (ref "LED34") (pin "A") (pinfunction "A_A") (pintype "passive"))
      (node (ref "LED35") (pin "A") (pinfunction "A_A") (pintype "passive"))
      (node (ref "LED36") (pin "A") (pinfunction "A_A") (pintype "passive"))
      (node (ref "LED37") (pin "A") (pinfunction "A_A") (pintype "passive"))
      (node (ref "LED38") (pin "A") (pinfunction "A_A") (pintype "passive"))
      (node (ref "LED39") (pin "A") (pinfunction "A_A") (pintype "passive"))
      (node (ref "LED40") (pin "A") (pinfunction "A_A") (pintype "passive"))
      (node (ref "Q5") (pin "E") (pinfunction "E_E") (pintype "passive"))
    )
    (net (code "35") (name "Net-(LED41-PadA)") (class "Default")
      (node (ref "LED41") (pin "A") (pinfunction "A_A") (pintype "passive"))
      (node (ref "LED42") (pin "A") (pinfunction "A_A") (pintype "passive"))
      (node (ref "LED43") (pin "A") (pinfunction "A_A") (pintype "passive"))
      (node (ref "LED44") (pin "A") (pinfunction "A_A") (pintype "passive"))
      (node (ref "LED45") (pin "A") (pinfunction "A_A") (pintype "passive"))
      (node (ref "LED46") (pin "A") (pinfunction "A_A") (pintype "passive"))
      (node (ref "LED47") (pin "A") (pinfunction "A_A") (pintype "passive"))
      (node (ref "LED48") (pin "A") (pinfunction "A_A") (pintype "passive"))
      (node (ref "Q6") (pin "E") (pinfunction "E_E") (pintype "passive"))
    )
    (net (code "36") (name "Net-(LED49-PadA)") (class "Default")
      (node (ref "LED49") (pin "A") (pinfunction "A_A") (pintype "passive"))
      (node (ref "LED50") (pin "A") (pinfunction "A_A") (pintype "passive"))
      (node (ref "LED51") (pin "A") (pinfunction "A_A") (pintype "passive"))
      (node (ref "LED52") (pin "A") (pinfunction "A_A") (pintype "passive"))
      (node (ref "LED53") (pin "A") (pinfunction "A_A") (pintype "passive"))
      (node (ref "LED54") (pin "A") (pinfunction "A_A") (pintype "passive"))
      (node (ref "LED55") (pin "A") (pinfunction "A_A") (pintype "passive"))
      (node (ref "LED56") (pin "A") (pinfunction "A_A") (pintype "passive"))
      (node (ref "Q7") (pin "E") (pinfunction "E_E") (pintype "passive"))
    )
    (net (code "37") (name "Net-(LED57-PadA)") (class "Default")
      (node (ref "LED57") (pin "A") (pinfunction "A_A") (pintype "passive"))
      (node (ref "LED58") (pin "A") (pinfunction "A_A") (pintype "passive"))
      (node (ref "LED59") (pin "A") (pinfunction "A_A") (pintype "passive"))
      (node (ref "LED60") (pin "A") (pinfunction "A_A") (pintype "passive"))
      (node (ref "LED61") (pin "A") (pinfunction "A_A") (pintype "passive"))
      (node (ref "LED62") (pin "A") (pinfunction "A_A") (pintype "passive"))
      (node (ref "LED63") (pin "A") (pinfunction "A_A") (pintype "passive"))
      (node (ref "LED64") (pin "A") (pinfunction "A_A") (pintype "passive"))
      (node (ref "Q8") (pin "E") (pinfunction "E_E") (pintype "passive"))
    )
    (net (code "38") (name "Net-(Q1-PadB)") (class "Default")
      (node (ref "Q1") (pin "B") (pinfunction "B_B") (pintype "passive"))
      (node (ref "R1") (pin "2") (pinfunction "2_2") (pintype "passive"))
    )
    (net (code "39") (name "Net-(Q2-PadB)") (class "Default")
      (node (ref "Q2") (pin "B") (pinfunction "B_B") (pintype "passive"))
      (node (ref "R2") (pin "2") (pinfunction "2_2") (pintype "passive"))
    )
    (net (code "40") (name "Net-(Q3-PadB)") (class "Default")
      (node (ref "Q3") (pin "B") (pinfunction "B_B") (pintype "passive"))
      (node (ref "R3") (pin "2") (pinfunction "2_2") (pintype "passive"))
    )
    (net (code "41") (name "Net-(Q4-PadB)") (class "Default")
      (node (ref "Q4") (pin "B") (pinfunction "B_B") (pintype "passive"))
      (node (ref "R4") (pin "2") (pinfunction "2_2") (pintype "passive"))
    )
    (net (code "42") (name "Net-(Q5-PadB)") (class "Default")
      (node (ref "Q5") (pin "B") (pinfunction "B_B") (pintype "passive"))
      (node (ref "R5") (pin "2") (pinfunction "2_2") (pintype "passive"))
    )
    (net (code "43") (name "Net-(Q6-PadB)") (class "Default")
      (node (ref "Q6") (pin "B") (pinfunction "B_B") (pintype "passive"))
      (node (ref "R6") (pin "2") (pinfunction "2_2") (pintype "passive"))
    )
    (net (code "44") (name "Net-(Q7-PadB)") (class "Default")
      (node (ref "Q7") (pin "B") (pinfunction "B_B") (pintype "passive"))
      (node (ref "R7") (pin "2") (pinfunction "2_2") (pintype "passive"))
    )
    (net (code "45") (name "Net-(Q8-PadB)") (class "Default")
      (node (ref "Q8") (pin "B") (pinfunction "B_B") (pintype "passive"))
      (node (ref "R8") (pin "2") (pinfunction "2_2") (pintype "passive"))
    )
    (net (code "46") (name "Net-(S1-S)") (class "Default")
      (node (ref "R10") (pin "2") (pinfunction "2_2") (pintype "passive"))
      (node (ref "R9") (pin "1") (pinfunction "1_1") (pintype "passive"))
      (node (ref "S1") (pin "1") (pinfunction "S_1") (pintype "passive"))
      (node (ref "S1") (pin "2") (pinfunction "S1_2") (pintype "passive"))
    )
    (net (code "47") (name "Net-(X1A-KL)") (class "Default")
      (node (ref "D1") (pin "A") (pinfunction "A_A") (pintype "passive"))
      (node (ref "X1") (pin "1") (pinfunction "KL_1") (pintype "passive"))
    )
    (net (code "48") (name "VCC") (class "Default")
      (node (ref "C2") (pin "1") (pinfunction "1_1") (pintype "passive"))
      (node (ref "C3") (pin "+") (pinfunction "+_+") (pintype "passive"))
      (node (ref "C4") (pin "1") (pinfunction "1_1") (pintype "passive"))
      (node (ref "IC1") (pin "9") (pinfunction "CLR_9") (pintype "input"))
      (node (ref "IC2") (pin "14") (pinfunction "VDD_14") (pintype "power_in"))
      (node (ref "IC3") (pin "3") (pinfunction "VO_3") (pintype "passive"))
      (node (ref "ICSP") (pin "2") (pinfunction "2_2") (pintype "passive"))
      (node (ref "Q1") (pin "C") (pinfunction "C_C") (pintype "passive"))
      (node (ref "Q2") (pin "C") (pinfunction "C_C") (pintype "passive"))
      (node (ref "Q3") (pin "C") (pinfunction "C_C") (pintype "passive"))
      (node (ref "Q4") (pin "C") (pinfunction "C_C") (pintype "passive"))
      (node (ref "Q5") (pin "C") (pinfunction "C_C") (pintype "passive"))
      (node (ref "Q6") (pin "C") (pinfunction "C_C") (pintype "passive"))
      (node (ref "Q7") (pin "C") (pinfunction "C_C") (pintype "passive"))
      (node (ref "Q8") (pin "C") (pinfunction "C_C") (pintype "passive"))
      (node (ref "R9") (pin "2") (pinfunction "2_2") (pintype "passive"))
    )
    (net (code "49") (name "unconnected-(IC2-RA0{slash}AN0-Pad17)") (class "Default")
      (node (ref "IC2") (pin "17") (pinfunction "RA0/AN0_17") (pintype "bidirectional"))
    )
    (net (code "50") (name "unconnected-(IC2-RA1{slash}AN1-Pad18)") (class "Default")
      (node (ref "IC2") (pin "18") (pinfunction "RA1/AN1_18") (pintype "bidirectional"))
    )
    (net (code "51") (name "unconnected-(IC2-RA4{slash}TOCKI{slash}CMP2-Pad3)") (class "Default")
      (node (ref "IC2") (pin "3") (pinfunction "RA4/TOCKI/CMP2_3") (pintype "bidirectional"))
    )
    (net (code "52") (name "unconnected-(IC2-RA6{slash}OSC2{slash}CLKOUT-Pad15)") (class "Default")
      (node (ref "IC2") (pin "15") (pinfunction "RA6/OSC2/CLKOUT_15") (pintype "bidirectional"))
    )
    (net (code "53") (name "unconnected-(IC2-RA7{slash}OSC1{slash}CLKIN-Pad16)") (class "Default")
      (node (ref "IC2") (pin "16") (pinfunction "RA7/OSC1/CLKIN_16") (pintype "bidirectional"))
    )
  )
)
